# USB-HUB-MUX.net
KiCad netlist of a schematic drawn in Altium Designer
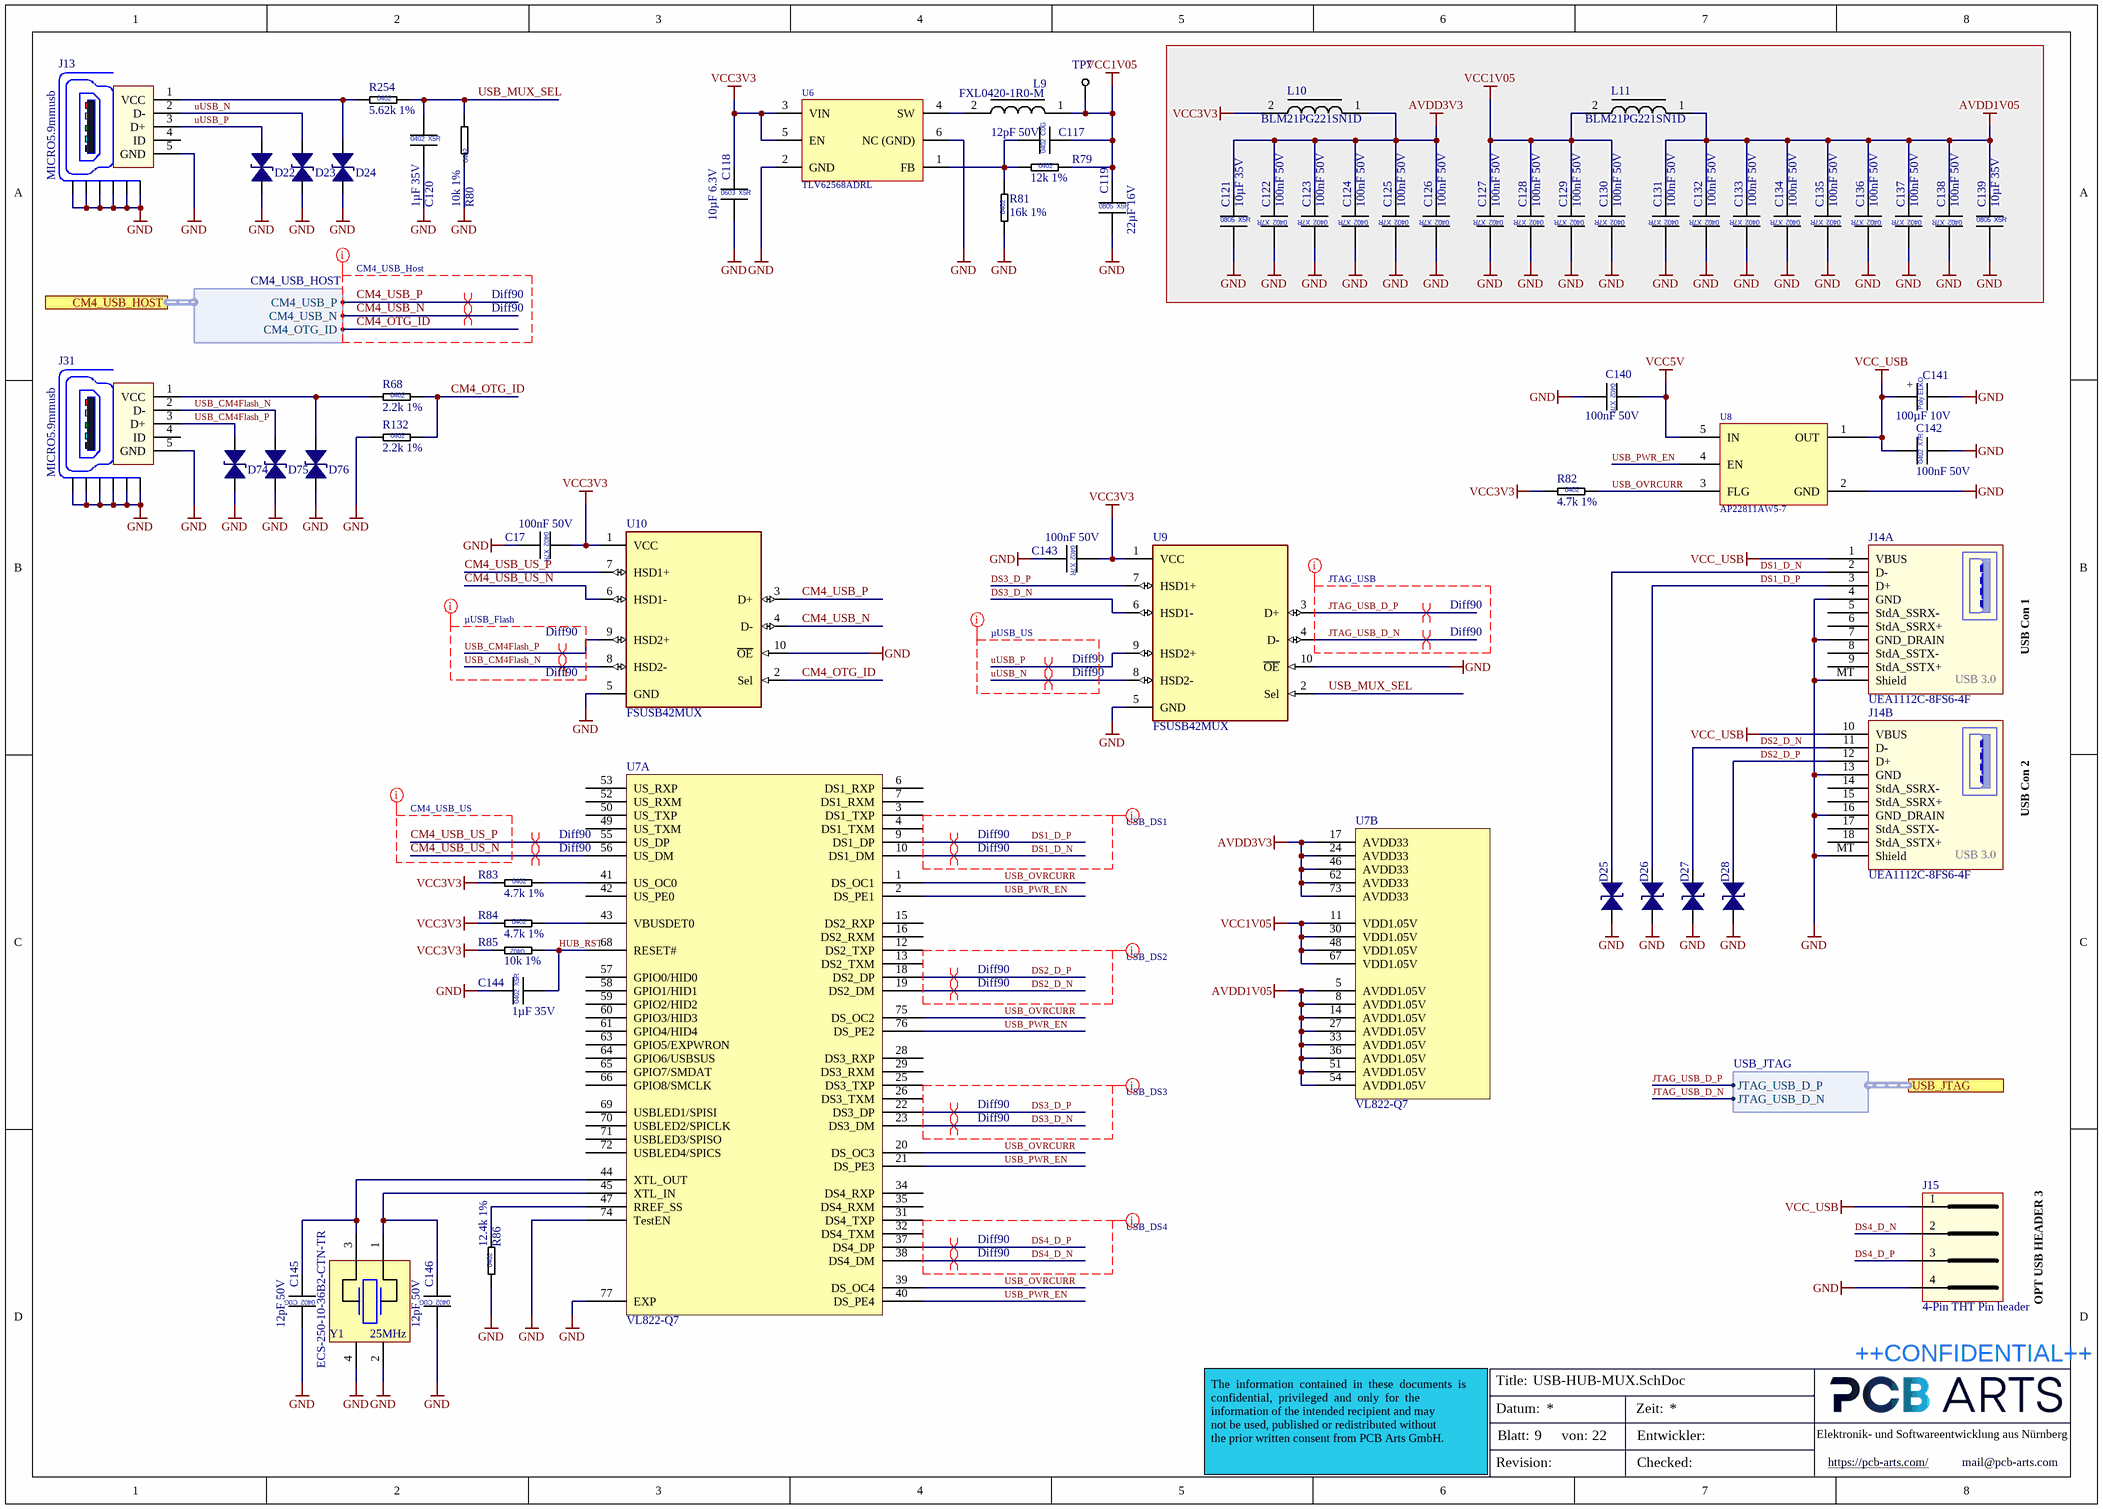
[diagram p0: USB-HUB-MUX.SchDoc]

(export (version "E")
  (design (tool "Eeschema 10.0.6"))
  (components
    (comp (ref "C17")
      (value "100nF 50V")
      (footprint "Cap:CAP_0402_L")
      (description "Multilayer Ceramic Capacitors MLCC - SMD/SMT 0402 50VDC")
      (libsource (lib "") (part "CAP_0402_100nF_50V_1"))
    )
    (comp (ref "C117")
      (value "12pF 50V")
      (footprint "Cap:CAP_0402_L")
      (description "Multilayer Ceramic Capacitors MLCC - SMD/SMT 0402 50VDC")
      (libsource (lib "Cap") (part "CAP_0402_12pF_50V"))
    )
    (comp (ref "C118")
      (value "10µF 6.3V")
      (footprint "Cap:CAP_0603_L")
      (description "Multilayer Ceramic Capacitors MLCC - SMD/SMT 0603 6.3VDC")
      (libsource (lib "Cap") (part "CAP_0603_10µF_6.3V"))
    )
    (comp (ref "C119")
      (value "22µF 16V")
      (footprint "Cap:CAP_0805")
      (description "Multilayer Ceramic Capacitors MLCC - SMD/SMT 0805 16VDC")
      (libsource (lib "Cap") (part "CAP_0805_22µF_16V"))
    )
    (comp (ref "C120")
      (value "1µF 35V")
      (footprint "Cap:CAP_0402_L")
      (description "Multilayer Ceramic Capacitors MLCC - SMD/SMT 0402 35VDC")
      (libsource (lib "Cap") (part "CAP_0402_1µF_35V"))
    )
    (comp (ref "C121")
      (value "10µF 35V")
      (footprint "Cap:CAP_0805")
      (description "Multilayer Ceramic Capacitors MLCC - SMD/SMT 0805 35VDC")
      (libsource (lib "Cap") (part "CAP_0805_10µF_35V"))
    )
    (comp (ref "C122")
      (value "100nF 50V")
      (footprint "Cap:CAP_0402_L")
      (description "Multilayer Ceramic Capacitors MLCC - SMD/SMT 0402 50VDC")
      (libsource (lib "Cap") (part "CAP_0402_100nF_50V"))
    )
    (comp (ref "C123")
      (value "100nF 50V")
      (footprint "Cap:CAP_0402_L")
      (description "Multilayer Ceramic Capacitors MLCC - SMD/SMT 0402 50VDC")
      (libsource (lib "Cap") (part "CAP_0402_100nF_50V"))
    )
    (comp (ref "C124")
      (value "100nF 50V")
      (footprint "Cap:CAP_0402_L")
      (description "Multilayer Ceramic Capacitors MLCC - SMD/SMT 0402 50VDC")
      (libsource (lib "Cap") (part "CAP_0402_100nF_50V"))
    )
    (comp (ref "C125")
      (value "100nF 50V")
      (footprint "Cap:CAP_0402_L")
      (description "Multilayer Ceramic Capacitors MLCC - SMD/SMT 0402 50VDC")
      (libsource (lib "Cap") (part "CAP_0402_100nF_50V"))
    )
    (comp (ref "C126")
      (value "100nF 50V")
      (footprint "Cap:CAP_0402_L")
      (description "Multilayer Ceramic Capacitors MLCC - SMD/SMT 0402 50VDC")
      (libsource (lib "Cap") (part "CAP_0402_100nF_50V"))
    )
    (comp (ref "C127")
      (value "100nF 50V")
      (footprint "Cap:CAP_0402_L")
      (description "Multilayer Ceramic Capacitors MLCC - SMD/SMT 0402 50VDC")
      (libsource (lib "Cap") (part "CAP_0402_100nF_50V"))
    )
    (comp (ref "C128")
      (value "100nF 50V")
      (footprint "Cap:CAP_0402_L")
      (description "Multilayer Ceramic Capacitors MLCC - SMD/SMT 0402 50VDC")
      (libsource (lib "Cap") (part "CAP_0402_100nF_50V"))
    )
    (comp (ref "C129")
      (value "100nF 50V")
      (footprint "Cap:CAP_0402_L")
      (description "Multilayer Ceramic Capacitors MLCC - SMD/SMT 0402 50VDC")
      (libsource (lib "Cap") (part "CAP_0402_100nF_50V"))
    )
    (comp (ref "C130")
      (value "100nF 50V")
      (footprint "Cap:CAP_0402_L")
      (description "Multilayer Ceramic Capacitors MLCC - SMD/SMT 0402 50VDC")
      (libsource (lib "Cap") (part "CAP_0402_100nF_50V"))
    )
    (comp (ref "C131")
      (value "100nF 50V")
      (footprint "Cap:CAP_0402_L")
      (description "Multilayer Ceramic Capacitors MLCC - SMD/SMT 0402 50VDC")
      (libsource (lib "Cap") (part "CAP_0402_100nF_50V"))
    )
    (comp (ref "C132")
      (value "100nF 50V")
      (footprint "Cap:CAP_0402_L")
      (description "Multilayer Ceramic Capacitors MLCC - SMD/SMT 0402 50VDC")
      (libsource (lib "Cap") (part "CAP_0402_100nF_50V"))
    )
    (comp (ref "C133")
      (value "100nF 50V")
      (footprint "Cap:CAP_0402_L")
      (description "Multilayer Ceramic Capacitors MLCC - SMD/SMT 0402 50VDC")
      (libsource (lib "Cap") (part "CAP_0402_100nF_50V"))
    )
    (comp (ref "C134")
      (value "100nF 50V")
      (footprint "Cap:CAP_0402_L")
      (description "Multilayer Ceramic Capacitors MLCC - SMD/SMT 0402 50VDC")
      (libsource (lib "Cap") (part "CAP_0402_100nF_50V"))
    )
    (comp (ref "C135")
      (value "100nF 50V")
      (footprint "Cap:CAP_0402_L")
      (description "Multilayer Ceramic Capacitors MLCC - SMD/SMT 0402 50VDC")
      (libsource (lib "Cap") (part "CAP_0402_100nF_50V"))
    )
    (comp (ref "C136")
      (value "100nF 50V")
      (footprint "Cap:CAP_0402_L")
      (description "Multilayer Ceramic Capacitors MLCC - SMD/SMT 0402 50VDC")
      (libsource (lib "Cap") (part "CAP_0402_100nF_50V"))
    )
    (comp (ref "C137")
      (value "100nF 50V")
      (footprint "Cap:CAP_0402_L")
      (description "Multilayer Ceramic Capacitors MLCC - SMD/SMT 0402 50VDC")
      (libsource (lib "Cap") (part "CAP_0402_100nF_50V"))
    )
    (comp (ref "C138")
      (value "100nF 50V")
      (footprint "Cap:CAP_0402_L")
      (description "Multilayer Ceramic Capacitors MLCC - SMD/SMT 0402 50VDC")
      (libsource (lib "Cap") (part "CAP_0402_100nF_50V"))
    )
    (comp (ref "C139")
      (value "10µF 35V")
      (footprint "Cap:CAP_0805")
      (description "Multilayer Ceramic Capacitors MLCC - SMD/SMT 0805 35VDC")
      (libsource (lib "Cap") (part "CAP_0805_10µF_35V"))
    )
    (comp (ref "C140")
      (value "100nF 50V")
      (footprint "Cap:CAP_0402_L")
      (description "Multilayer Ceramic Capacitors MLCC - SMD/SMT 0402 50VDC")
      (libsource (lib "") (part "CAP_0402_100nF_50V_1"))
    )
    (comp (ref "C141")
      (value "100µF 10V")
      (footprint "Cap:WCAP-ASLI_D5H5.5")
      (description "Organische Polymer-Aluminiumkondensatoren 100uF 10 Volts 20%")
      (libsource (lib "Cap") (part "CAP_D5L5.5_100µF_10V"))
    )
    (comp (ref "C142")
      (value "100nF 50V")
      (footprint "Cap:CAP_0402_L")
      (description "Multilayer Ceramic Capacitors MLCC - SMD/SMT 0402 50VDC")
      (libsource (lib "Cap") (part "CAP_0402_100nF_50V"))
    )
    (comp (ref "C143")
      (value "100nF 50V")
      (footprint "Cap:CAP_0402_L")
      (description "Multilayer Ceramic Capacitors MLCC - SMD/SMT 0402 50VDC")
      (libsource (lib "") (part "CAP_0402_100nF_50V_1"))
    )
    (comp (ref "C144")
      (value "1µF 35V")
      (footprint "Cap:CAP_0402_L")
      (description "Multilayer Ceramic Capacitors MLCC - SMD/SMT 0402 35VDC")
      (libsource (lib "") (part "CAP_0402_1µF_35V_1"))
    )
    (comp (ref "C145")
      (value "12pF 50V")
      (footprint "Cap:CAP_0402_L")
      (description "Multilayer Ceramic Capacitors MLCC - SMD/SMT 0402 50VDC")
      (libsource (lib "Cap") (part "CAP_0402_12pF_50V"))
    )
    (comp (ref "C146")
      (value "12pF 50V")
      (footprint "Cap:CAP_0402_L")
      (description "Multilayer Ceramic Capacitors MLCC - SMD/SMT 0402 50VDC")
      (libsource (lib "Cap") (part "CAP_0402_12pF_50V"))
    )
    (comp (ref "D22")
      (value "CESDP0402UC5VB")
      (footprint "Protec:TVS_0402")
      (description "Low Capacitance ESD Protection Diode 0402")
      (libsource (lib "Protec") (part "CESDP0402UC5VB_TVS Diode 0402"))
    )
    (comp (ref "D23")
      (value "CESDP0402UC5VB")
      (footprint "Protec:TVS_0402")
      (description "Low Capacitance ESD Protection Diode 0402")
      (libsource (lib "Protec") (part "CESDP0402UC5VB_TVS Diode 0402"))
    )
    (comp (ref "D24")
      (value "CESDP0402UC5VB")
      (footprint "Protec:TVS_0402")
      (description "Low Capacitance ESD Protection Diode 0402")
      (libsource (lib "Protec") (part "CESDP0402UC5VB_TVS Diode 0402"))
    )
    (comp (ref "D25")
      (value "CESDP0402UC5VB")
      (footprint "Protec:TVS_0402")
      (description "Low Capacitance ESD Protection Diode 0402")
      (libsource (lib "Protec") (part "CESDP0402UC5VB_TVS Diode 0402"))
    )
    (comp (ref "D26")
      (value "CESDP0402UC5VB")
      (footprint "Protec:TVS_0402")
      (description "Low Capacitance ESD Protection Diode 0402")
      (libsource (lib "Protec") (part "CESDP0402UC5VB_TVS Diode 0402"))
    )
    (comp (ref "D27")
      (value "CESDP0402UC5VB")
      (footprint "Protec:TVS_0402")
      (description "Low Capacitance ESD Protection Diode 0402")
      (libsource (lib "Protec") (part "CESDP0402UC5VB_TVS Diode 0402"))
    )
    (comp (ref "D28")
      (value "CESDP0402UC5VB")
      (footprint "Protec:TVS_0402")
      (description "Low Capacitance ESD Protection Diode 0402")
      (libsource (lib "Protec") (part "CESDP0402UC5VB_TVS Diode 0402"))
    )
    (comp (ref "D74")
      (value "CESDP0402UC5VB")
      (footprint "Protec:TVS_0402")
      (description "Low Capacitance ESD Protection Diode 0402")
      (libsource (lib "Protec") (part "CESDP0402UC5VB_TVS Diode 0402"))
    )
    (comp (ref "D75")
      (value "CESDP0402UC5VB")
      (footprint "Protec:TVS_0402")
      (description "Low Capacitance ESD Protection Diode 0402")
      (libsource (lib "Protec") (part "CESDP0402UC5VB_TVS Diode 0402"))
    )
    (comp (ref "D76")
      (value "CESDP0402UC5VB")
      (footprint "Protec:TVS_0402")
      (description "Low Capacitance ESD Protection Diode 0402")
      (libsource (lib "Protec") (part "CESDP0402UC5VB_TVS Diode 0402"))
    )
    (comp (ref "J13")
      (value "MICRO5.9mmusb")
      (footprint "Conn:MICRO5.9mmusb")
      (description "SHOU HAN  MICRO5.9mmusb")
      (libsource (lib "Conn") (part "SMD micro USB Connector Horizontal C393940"))
    )
    (comp (ref "J14")
      (value "UEA1112C-8FS6-4F")
      (footprint "CONN:UEA1112C-8FS6-4F")
      (description "Dual USB 3.0 Horizontal Type A")
      (libsource (lib "Conn") (part "UEA1112C-8FS6-4F_Dual USB 3.0 Horizontal Type A_1"))
    )
    (comp (ref "J15")
      (value "4-Pin THT Pin header")
      (footprint "Conn:61300411121")
      (description "WR-PHD 2.54mm 4Pin THT Header")
      (libsource (lib "Conn") (part "61300411121_WR-PHD 2.54mm 4Pin THT Header"))
    )
    (comp (ref "J31")
      (value "MICRO5.9mmusb")
      (footprint "Conn:MICRO5.9mmusb")
      (description "SHOU HAN  MICRO5.9mmusb")
      (libsource (lib "Conn") (part "SMD micro USB Connector Horizontal C393940"))
    )
    (comp (ref "L9")
      (value "FXL0420-1R0-M")
      (footprint "Indc:FXL0420-1R0-M")
      (description "1uH ±20% 6A 27mΩ SMD,4.4x4.5x1.8mm Power Inductor")
      (libsource (lib "Indc") (part "1uH 6A 27mΩ  FXL0420-1R0-M"))
    )
    (comp (ref "L10")
      (value "BLM21PG221SN1D")
      (footprint "indc:L_0805")
      (description "Ferrite Beads 0805 220 OHM")
      (libsource (lib "Indc") (part "Ferrite Beads 0805 220 OHM BLM21PG221SN1D"))
    )
    (comp (ref "L11")
      (value "BLM21PG221SN1D")
      (footprint "indc:L_0805")
      (description "Ferrite Beads 0805 220 OHM")
      (libsource (lib "Indc") (part "Ferrite Beads 0805 220 OHM BLM21PG221SN1D"))
    )
    (comp (ref "R68")
      (value "2.2k 1%")
      (footprint "Res:RES_0402_L")
      (description "Thick Film Resistors - SMD 2.2kOhm 1%")
      (libsource (lib "Res") (part "RES_0402_2.2k_1%"))
    )
    (comp (ref "R79")
      (value "12k 1%")
      (footprint "Res:RES_0402_L")
      (description "Thick Film Resistors - SMD 12kOhm 1%")
      (libsource (lib "Res") (part "RES_0402_12k_1%"))
    )
    (comp (ref "R80")
      (value "10k 1%")
      (footprint "Res:RES_0402_L")
      (description "Thick Film Resistors - SMD 10kOhm 1%")
      (libsource (lib "Res") (part "RES_0402_10k_1%"))
    )
    (comp (ref "R81")
      (value "16k 1%")
      (footprint "Res:RES_0402_L")
      (description "Thick Film Resistors - SMD 16kOhm 1%")
      (libsource (lib "Res") (part "RES_0402_16k_1%"))
    )
    (comp (ref "R82")
      (value "4.7k 1%")
      (footprint "Res:RES_0402_L")
      (description "Thick Film Resistors - SMD 4.7kOhm 1%")
      (libsource (lib "Res") (part "RES_0402_4.7k_1%"))
    )
    (comp (ref "R83")
      (value "4.7k 1%")
      (footprint "Res:RES_0402_L")
      (description "Thick Film Resistors - SMD 4.7kOhm 1%")
      (libsource (lib "Res") (part "RES_0402_4.7k_1%"))
    )
    (comp (ref "R84")
      (value "4.7k 1%")
      (footprint "Res:RES_0402_L")
      (description "Thick Film Resistors - SMD 4.7kOhm 1%")
      (libsource (lib "Res") (part "RES_0402_4.7k_1%"))
    )
    (comp (ref "R85")
      (value "10k 1%")
      (footprint "Res:RES_0402_L")
      (description "Thick Film Resistors - SMD 10kOhm 1%")
      (libsource (lib "Res") (part "RES_0402_10k_1%"))
    )
    (comp (ref "R86")
      (value "12.4k 1%")
      (footprint "Res:RES_0402_L")
      (description "Thick Film Resistors - SMD 12.4kOhm 1%")
      (libsource (lib "Res") (part "RES_0402_12.4k_1%"))
    )
    (comp (ref "R132")
      (value "2.2k 1%")
      (footprint "Res:RES_0402_L")
      (description "Thick Film Resistors - SMD 2.2kOhm 1%")
      (libsource (lib "Res") (part "RES_0402_2.2k_1%"))
    )
    (comp (ref "R254")
      (value "5.62k 1%")
      (footprint "Res:RES_0402_L")
      (description "Thick Film Resistors - SMD 5.62kOhm 1%")
      (libsource (lib "Res") (part "RES_0402_5.62k_1%"))
    )
    (comp (ref "TP7")
      (value "Testpoint")
      (footprint "Electro_mech:Testpoint 0.8mm")
      (description "Testpoint 0.8mm")
      (libsource (lib "Electro_Mech") (part "Testpoint 0.8mm"))
    )
    (comp (ref "U6")
      (value "TLV62568ADRL")
      (footprint "Power:SON50P150X80-6N")
      (description "Step Down Converter with Forced PWM in SOT563 Package")
      (libsource (lib "Power") (part "TLV62568ADRL_Step Down Converter 1A; 2A"))
    )
    (comp (ref "U7")
      (value "VL822-Q7")
      (footprint "Digital:QFN50P900X900X85-76N")
      (description "USB Interface IC  USB 3.1 Hub 4 Ports")
      (libsource (lib "Digital") (part "VL822-Q7_USB Interface IC  USB 3.1 Hub 4 Ports"))
    )
    (comp (ref "U8")
      (value "AP22811AW5-7")
      (footprint "Power:SOT95P285X140-5N")
      (description "Power Switch ICs - Power Distribution Load Switch")
      (libsource (lib "Power") (part "AP22811AW5-7_Power Switch ICs - Power Distribution Load Switch"))
    )
    (comp (ref "U9")
      (value "FSUSB42MUX")
      (footprint "digital:SOP50P300X300X110-10N")
      (description "IC USB SWITCH DPDT")
      (libsource (lib "Digital") (part "FSUSB42MUX_IC USB SWITCH DPDT"))
    )
    (comp (ref "U10")
      (value "FSUSB42MUX")
      (footprint "digital:SOP50P300X300X110-10N")
      (description "IC USB SWITCH DPDT")
      (libsource (lib "Digital") (part "FSUSB42MUX_IC USB SWITCH DPDT"))
    )
    (comp (ref "Y1")
      (value "ECS-250-10-36B2-CTN-TR")
      (footprint "Timer:ECX-2236B")
      (description "2.5 x 2.0 x 0.55 mm SMD Crystal")
      (fields (field (name "FREQUENCY") "25MHz"))
      (libsource (lib "Timer") (part "Quarz 25MHz ESR 50R10pF"))
    )
  )
  (nets
    (net (code "3") (name "/CM4_OTG_ID") (class "Default")
      (node (ref "R132") (pin "2") (pinfunction "2_2") (pintype "passive"))
      (node (ref "R68") (pin "2") (pinfunction "2_2") (pintype "passive"))
      (node (ref "U10") (pin "2") (pinfunction "Sel_2") (pintype "input"))
    )
    (net (code "4") (name "/CM4_USB_N") (class "Default")
      (node (ref "U10") (pin "4") (pinfunction "D-_4") (pintype "bidirectional"))
    )
    (net (code "5") (name "/CM4_USB_P") (class "Default")
      (node (ref "U10") (pin "3") (pinfunction "D+_3") (pintype "bidirectional"))
    )
    (net (code "6") (name "/CM4_USB_US_N") (class "Default")
      (node (ref "U10") (pin "6") (pinfunction "HSD1-_6") (pintype "bidirectional"))
      (node (ref "U7") (pin "56") (pinfunction "US_DM_56") (pintype "passive"))
    )
    (net (code "7") (name "/CM4_USB_US_P") (class "Default")
      (node (ref "U10") (pin "7") (pinfunction "HSD1+_7") (pintype "bidirectional"))
      (node (ref "U7") (pin "55") (pinfunction "US_DP_55") (pintype "passive"))
    )
    (net (code "8") (name "/DS1_D_N") (class "Default")
      (node (ref "D25") (pin "2") (pinfunction "2_2") (pintype "passive"))
      (node (ref "J14") (pin "2") (pinfunction "D-_2") (pintype "passive"))
      (node (ref "U7") (pin "10") (pinfunction "DS1_DM_10") (pintype "passive"))
    )
    (net (code "9") (name "/DS1_D_P") (class "Default")
      (node (ref "D26") (pin "2") (pinfunction "2_2") (pintype "passive"))
      (node (ref "J14") (pin "3") (pinfunction "D+_3") (pintype "passive"))
      (node (ref "U7") (pin "9") (pinfunction "DS1_DP_9") (pintype "passive"))
    )
    (net (code "10") (name "/DS2_D_N") (class "Default")
      (node (ref "D27") (pin "2") (pinfunction "2_2") (pintype "passive"))
      (node (ref "J14") (pin "11") (pinfunction "D-_11") (pintype "passive"))
      (node (ref "U7") (pin "19") (pinfunction "DS2_DM_19") (pintype "passive"))
    )
    (net (code "11") (name "/DS2_D_P") (class "Default")
      (node (ref "D28") (pin "2") (pinfunction "2_2") (pintype "passive"))
      (node (ref "J14") (pin "12") (pinfunction "D+_12") (pintype "passive"))
      (node (ref "U7") (pin "18") (pinfunction "DS2_DP_18") (pintype "passive"))
    )
    (net (code "12") (name "/DS3_D_N") (class "Default")
      (node (ref "U7") (pin "23") (pinfunction "DS3_DM_23") (pintype "passive"))
      (node (ref "U9") (pin "6") (pinfunction "HSD1-_6") (pintype "bidirectional"))
    )
    (net (code "13") (name "/DS3_D_P") (class "Default")
      (node (ref "U7") (pin "22") (pinfunction "DS3_DP_22") (pintype "passive"))
      (node (ref "U9") (pin "7") (pinfunction "HSD1+_7") (pintype "bidirectional"))
    )
    (net (code "14") (name "/DS4_D_N") (class "Default")
      (node (ref "J15") (pin "2") (pinfunction "2_2") (pintype "passive"))
      (node (ref "U7") (pin "38") (pinfunction "DS4_DM_38") (pintype "passive"))
    )
    (net (code "15") (name "/DS4_D_P") (class "Default")
      (node (ref "J15") (pin "3") (pinfunction "3_3") (pintype "passive"))
      (node (ref "U7") (pin "37") (pinfunction "DS4_DP_37") (pintype "passive"))
    )
    (net (code "16") (name "/HUB_RST") (class "Default")
      (node (ref "C144") (pin "2") (pinfunction "2_2") (pintype "passive"))
      (node (ref "R85") (pin "1") (pinfunction "1_1") (pintype "passive"))
      (node (ref "U7") (pin "68") (pinfunction "RESET#_68") (pintype "passive"))
    )
    (net (code "17") (name "/JTAG_USB_D_N") (class "Default")
      (node (ref "U9") (pin "4") (pinfunction "D-_4") (pintype "bidirectional"))
    )
    (net (code "18") (name "/JTAG_USB_D_P") (class "Default")
      (node (ref "U9") (pin "3") (pinfunction "D+_3") (pintype "bidirectional"))
    )
    (net (code "19") (name "/USB_CM4Flash_N") (class "Default")
      (node (ref "D75") (pin "1") (pinfunction "1_1") (pintype "passive"))
      (node (ref "J31") (pin "2") (pinfunction "D-_2") (pintype "passive"))
      (node (ref "U10") (pin "8") (pinfunction "HSD2-_8") (pintype "bidirectional"))
    )
    (net (code "20") (name "/USB_CM4Flash_P") (class "Default")
      (node (ref "D74") (pin "1") (pinfunction "1_1") (pintype "passive"))
      (node (ref "J31") (pin "3") (pinfunction "D+_3") (pintype "passive"))
      (node (ref "U10") (pin "9") (pinfunction "HSD2+_9") (pintype "bidirectional"))
    )
    (net (code "21") (name "/USB_MUX_SEL") (class "Default")
      (node (ref "C120") (pin "1") (pinfunction "1_1") (pintype "passive"))
      (node (ref "R254") (pin "2") (pinfunction "2_2") (pintype "passive"))
      (node (ref "R80") (pin "2") (pinfunction "2_2") (pintype "passive"))
      (node (ref "U9") (pin "2") (pinfunction "Sel_2") (pintype "input"))
    )
    (net (code "22") (name "/USB_OVRCURR") (class "Default")
      (node (ref "R82") (pin "2") (pinfunction "2_2") (pintype "passive"))
      (node (ref "U7") (pin "1") (pinfunction "DS_OC1_1") (pintype "passive"))
      (node (ref "U7") (pin "20") (pinfunction "DS_OC3_20") (pintype "passive"))
      (node (ref "U7") (pin "39") (pinfunction "DS_OC4_39") (pintype "passive"))
      (node (ref "U7") (pin "75") (pinfunction "DS_OC2_75") (pintype "passive"))
      (node (ref "U8") (pin "3") (pinfunction "FLG_3") (pintype "open_collector"))
    )
    (net (code "23") (name "/USB_PWR_EN") (class "Default")
      (node (ref "U7") (pin "2") (pinfunction "DS_PE1_2") (pintype "passive"))
      (node (ref "U7") (pin "21") (pinfunction "DS_PE3_21") (pintype "passive"))
      (node (ref "U7") (pin "40") (pinfunction "DS_PE4_40") (pintype "passive"))
      (node (ref "U7") (pin "76") (pinfunction "DS_PE2_76") (pintype "passive"))
      (node (ref "U8") (pin "4") (pinfunction "EN_4") (pintype "passive"))
    )
    (net (code "24") (name "/uUSB_N") (class "Default")
      (node (ref "D23") (pin "1") (pinfunction "1_1") (pintype "passive"))
      (node (ref "J13") (pin "2") (pinfunction "D-_2") (pintype "passive"))
      (node (ref "U9") (pin "8") (pinfunction "HSD2-_8") (pintype "bidirectional"))
    )
    (net (code "25") (name "/uUSB_P") (class "Default")
      (node (ref "D22") (pin "1") (pinfunction "1_1") (pintype "passive"))
      (node (ref "J13") (pin "3") (pinfunction "D+_3") (pintype "passive"))
      (node (ref "U9") (pin "9") (pinfunction "HSD2+_9") (pintype "bidirectional"))
    )
    (net (code "28") (name "AVDD1V05") (class "Default")
      (node (ref "C131") (pin "2") (pinfunction "2_2") (pintype "passive"))
      (node (ref "C132") (pin "2") (pinfunction "2_2") (pintype "passive"))
      (node (ref "C133") (pin "2") (pinfunction "2_2") (pintype "passive"))
      (node (ref "C134") (pin "2") (pinfunction "2_2") (pintype "passive"))
      (node (ref "C135") (pin "2") (pinfunction "2_2") (pintype "passive"))
      (node (ref "C136") (pin "2") (pinfunction "2_2") (pintype "passive"))
      (node (ref "C137") (pin "2") (pinfunction "2_2") (pintype "passive"))
      (node (ref "C138") (pin "2") (pinfunction "2_2") (pintype "passive"))
      (node (ref "C139") (pin "1") (pinfunction "1_1") (pintype "passive"))
      (node (ref "L11") (pin "1") (pinfunction "1_1") (pintype "passive"))
      (node (ref "U7") (pin "14") (pinfunction "AVDD1.05V_14") (pintype "passive"))
      (node (ref "U7") (pin "27") (pinfunction "AVDD1.05V_27") (pintype "passive"))
      (node (ref "U7") (pin "33") (pinfunction "AVDD1.05V_33") (pintype "passive"))
      (node (ref "U7") (pin "36") (pinfunction "AVDD1.05V_36") (pintype "passive"))
      (node (ref "U7") (pin "5") (pinfunction "AVDD1.05V_5") (pintype "passive"))
      (node (ref "U7") (pin "51") (pinfunction "AVDD1.05V_51") (pintype "passive"))
      (node (ref "U7") (pin "54") (pinfunction "AVDD1.05V_54") (pintype "passive"))
      (node (ref "U7") (pin "8") (pinfunction "AVDD1.05V_8") (pintype "passive"))
    )
    (net (code "29") (name "AVDD3V3") (class "Default")
      (node (ref "C121") (pin "1") (pinfunction "1_1") (pintype "passive"))
      (node (ref "C122") (pin "2") (pinfunction "2_2") (pintype "passive"))
      (node (ref "C123") (pin "2") (pinfunction "2_2") (pintype "passive"))
      (node (ref "C124") (pin "2") (pinfunction "2_2") (pintype "passive"))
      (node (ref "C125") (pin "2") (pinfunction "2_2") (pintype "passive"))
      (node (ref "C126") (pin "2") (pinfunction "2_2") (pintype "passive"))
      (node (ref "L10") (pin "1") (pinfunction "1_1") (pintype "passive"))
      (node (ref "U7") (pin "17") (pinfunction "AVDD33_17") (pintype "passive"))
      (node (ref "U7") (pin "24") (pinfunction "AVDD33_24") (pintype "passive"))
      (node (ref "U7") (pin "46") (pinfunction "AVDD33_46") (pintype "passive"))
      (node (ref "U7") (pin "62") (pinfunction "AVDD33_62") (pintype "passive"))
      (node (ref "U7") (pin "73") (pinfunction "AVDD33_73") (pintype "passive"))
    )
    (net (code "30") (name "GND") (class "Default")
      (node (ref "C118") (pin "2") (pinfunction "2_2") (pintype "passive"))
      (node (ref "C119") (pin "2") (pinfunction "2_2") (pintype "passive"))
      (node (ref "C120") (pin "2") (pinfunction "2_2") (pintype "passive"))
      (node (ref "C121") (pin "2") (pinfunction "2_2") (pintype "passive"))
      (node (ref "C122") (pin "1") (pinfunction "1_1") (pintype "passive"))
      (node (ref "C123") (pin "1") (pinfunction "1_1") (pintype "passive"))
      (node (ref "C124") (pin "1") (pinfunction "1_1") (pintype "passive"))
      (node (ref "C125") (pin "1") (pinfunction "1_1") (pintype "passive"))
      (node (ref "C126") (pin "1") (pinfunction "1_1") (pintype "passive"))
      (node (ref "C127") (pin "1") (pinfunction "1_1") (pintype "passive"))
      (node (ref "C128") (pin "1") (pinfunction "1_1") (pintype "passive"))
      (node (ref "C129") (pin "1") (pinfunction "1_1") (pintype "passive"))
      (node (ref "C130") (pin "1") (pinfunction "1_1") (pintype "passive"))
      (node (ref "C131") (pin "1") (pinfunction "1_1") (pintype "passive"))
      (node (ref "C132") (pin "1") (pinfunction "1_1") (pintype "passive"))
      (node (ref "C133") (pin "1") (pinfunction "1_1") (pintype "passive"))
      (node (ref "C134") (pin "1") (pinfunction "1_1") (pintype "passive"))
      (node (ref "C135") (pin "1") (pinfunction "1_1") (pintype "passive"))
      (node (ref "C136") (pin "1") (pinfunction "1_1") (pintype "passive"))
      (node (ref "C137") (pin "1") (pinfunction "1_1") (pintype "passive"))
      (node (ref "C138") (pin "1") (pinfunction "1_1") (pintype "passive"))
      (node (ref "C139") (pin "2") (pinfunction "2_2") (pintype "passive"))
      (node (ref "C140") (pin "2") (pinfunction "2_2") (pintype "passive"))
      (node (ref "C141") (pin "2") (pinfunction "2_2") (pintype "passive"))
      (node (ref "C142") (pin "2") (pinfunction "2_2") (pintype "passive"))
      (node (ref "C143") (pin "2") (pinfunction "2_2") (pintype "passive"))
      (node (ref "C144") (pin "1") (pinfunction "1_1") (pintype "passive"))
      (node (ref "C145") (pin "1") (pinfunction "1_1") (pintype "passive"))
      (node (ref "C146") (pin "1") (pinfunction "1_1") (pintype "passive"))
      (node (ref "C17") (pin "2") (pinfunction "2_2") (pintype "passive"))
      (node (ref "D22") (pin "2") (pinfunction "2_2") (pintype "passive"))
      (node (ref "D23") (pin "2") (pinfunction "2_2") (pintype "passive"))
      (node (ref "D24") (pin "2") (pinfunction "2_2") (pintype "passive"))
      (node (ref "D25") (pin "1") (pinfunction "1_1") (pintype "passive"))
      (node (ref "D26") (pin "1") (pinfunction "1_1") (pintype "passive"))
      (node (ref "D27") (pin "1") (pinfunction "1_1") (pintype "passive"))
      (node (ref "D28") (pin "1") (pinfunction "1_1") (pintype "passive"))
      (node (ref "D74") (pin "2") (pinfunction "2_2") (pintype "passive"))
      (node (ref "D75") (pin "2") (pinfunction "2_2") (pintype "passive"))
      (node (ref "D76") (pin "2") (pinfunction "2_2") (pintype "passive"))
      (node (ref "J13") (pin "10") (pinfunction "Shield_10") (pintype "passive"))
      (node (ref "J13") (pin "11") (pinfunction "Shield_11") (pintype "passive"))
      (node (ref "J13") (pin "5") (pinfunction "GND_5") (pintype "passive"))
      (node (ref "J13") (pin "6") (pinfunction "Shield_6") (pintype "passive"))
      (node (ref "J13") (pin "7") (pinfunction "Shield_7") (pintype "passive"))
      (node (ref "J13") (pin "8") (pinfunction "Shield_8") (pintype "passive"))
      (node (ref "J13") (pin "9") (pinfunction "Shield_9") (pintype "passive"))
      (node (ref "J14") (pin "13") (pinfunction "GND_13") (pintype "passive"))
      (node (ref "J14") (pin "16") (pinfunction "GND_DRAIN_16") (pintype "passive"))
      (node (ref "J14") (pin "4") (pinfunction "GND_4") (pintype "passive"))
      (node (ref "J14") (pin "7") (pinfunction "GND_DRAIN_7") (pintype "passive"))
      (node (ref "J14") (pin "MT") (pinfunction "Shield_MT") (pintype "passive"))
      (node (ref "J15") (pin "4") (pinfunction "4_4") (pintype "passive"))
      (node (ref "J31") (pin "10") (pinfunction "Shield_10") (pintype "passive"))
      (node (ref "J31") (pin "11") (pinfunction "Shield_11") (pintype "passive"))
      (node (ref "J31") (pin "5") (pinfunction "GND_5") (pintype "passive"))
      (node (ref "J31") (pin "6") (pinfunction "Shield_6") (pintype "passive"))
      (node (ref "J31") (pin "7") (pinfunction "Shield_7") (pintype "passive"))
      (node (ref "J31") (pin "8") (pinfunction "Shield_8") (pintype "passive"))
      (node (ref "J31") (pin "9") (pinfunction "Shield_9") (pintype "passive"))
      (node (ref "R132") (pin "1") (pinfunction "1_1") (pintype "passive"))
      (node (ref "R80") (pin "1") (pinfunction "1_1") (pintype "passive"))
      (node (ref "R81") (pin "1") (pinfunction "1_1") (pintype "passive"))
      (node (ref "R86") (pin "1") (pinfunction "1_1") (pintype "passive"))
      (node (ref "U10") (pin "10") (pinfunction "~{OE}_10") (pintype "input"))
      (node (ref "U10") (pin "5") (pinfunction "GND_5") (pintype "power_in"))
      (node (ref "U6") (pin "2") (pinfunction "GND_2") (pintype "passive"))
      (node (ref "U6") (pin "6") (pinfunction "NC_(GND)_6") (pintype "passive"))
      (node (ref "U7") (pin "74") (pinfunction "TestEN_74") (pintype "passive"))
      (node (ref "U7") (pin "77") (pinfunction "EXP_77") (pintype "passive"))
      (node (ref "U8") (pin "2") (pinfunction "GND_2") (pintype "power_in"))
      (node (ref "U9") (pin "10") (pinfunction "~{OE}_10") (pintype "input"))
      (node (ref "U9") (pin "5") (pinfunction "GND_5") (pintype "power_in"))
      (node (ref "Y1") (pin "2") (pinfunction "2_2") (pintype "passive"))
      (node (ref "Y1") (pin "4") (pinfunction "4_4") (pintype "passive"))
    )
    (net (code "31") (name "Net-(J13-VCC)") (class "Default")
      (node (ref "D24") (pin "1") (pinfunction "1_1") (pintype "passive"))
      (node (ref "J13") (pin "1") (pinfunction "VCC_1") (pintype "passive"))
      (node (ref "R254") (pin "1") (pinfunction "1_1") (pintype "passive"))
    )
    (net (code "32") (name "Net-(J31-VCC)") (class "Default")
      (node (ref "D76") (pin "1") (pinfunction "1_1") (pintype "passive"))
      (node (ref "J31") (pin "1") (pinfunction "VCC_1") (pintype "passive"))
      (node (ref "R68") (pin "1") (pinfunction "1_1") (pintype "passive"))
    )
    (net (code "33") (name "Net-(U6-FB)") (class "Default")
      (node (ref "C117") (pin "1") (pinfunction "1_1") (pintype "passive"))
      (node (ref "R79") (pin "1") (pinfunction "1_1") (pintype "passive"))
      (node (ref "R81") (pin "2") (pinfunction "2_2") (pintype "passive"))
      (node (ref "U6") (pin "1") (pinfunction "FB_1") (pintype "passive"))
    )
    (net (code "34") (name "Net-(U6-SW)") (class "Default")
      (node (ref "L9") (pin "2") (pinfunction "2_2") (pintype "passive"))
      (node (ref "U6") (pin "4") (pinfunction "SW_4") (pintype "passive"))
    )
    (net (code "35") (name "Net-(U7A-RREF_SS)") (class "Default")
      (node (ref "R86") (pin "2") (pinfunction "2_2") (pintype "passive"))
      (node (ref "U7") (pin "47") (pinfunction "RREF_SS_47") (pintype "passive"))
    )
    (net (code "36") (name "Net-(U7A-US_OC0)") (class "Default")
      (node (ref "R83") (pin "2") (pinfunction "2_2") (pintype "passive"))
      (node (ref "U7") (pin "41") (pinfunction "US_OC0_41") (pintype "passive"))
    )
    (net (code "37") (name "Net-(U7A-VBUSDET0)") (class "Default")
      (node (ref "R84") (pin "2") (pinfunction "2_2") (pintype "passive"))
      (node (ref "U7") (pin "43") (pinfunction "VBUSDET0_43") (pintype "passive"))
    )
    (net (code "38") (name "Net-(U7A-XTL_IN)") (class "Default")
      (node (ref "C146") (pin "2") (pinfunction "2_2") (pintype "passive"))
      (node (ref "U7") (pin "45") (pinfunction "XTL_IN_45") (pintype "passive"))
      (node (ref "Y1") (pin "1") (pinfunction "1_1") (pintype "passive"))
    )
    (net (code "39") (name "Net-(U7A-XTL_OUT)") (class "Default")
      (node (ref "C145") (pin "2") (pinfunction "2_2") (pintype "passive"))
      (node (ref "U7") (pin "44") (pinfunction "XTL_OUT_44") (pintype "passive"))
      (node (ref "Y1") (pin "3") (pinfunction "3_3") (pintype "passive"))
    )
    (net (code "40") (name "VCC1V05") (class "Default")
      (node (ref "C117") (pin "2") (pinfunction "2_2") (pintype "passive"))
      (node (ref "C119") (pin "1") (pinfunction "1_1") (pintype "passive"))
      (node (ref "C127") (pin "2") (pinfunction "2_2") (pintype "passive"))
      (node (ref "C128") (pin "2") (pinfunction "2_2") (pintype "passive"))
      (node (ref "C129") (pin "2") (pinfunction "2_2") (pintype "passive"))
      (node (ref "C130") (pin "2") (pinfunction "2_2") (pintype "passive"))
      (node (ref "L11") (pin "2") (pinfunction "2_2") (pintype "passive"))
      (node (ref "L9") (pin "1") (pinfunction "1_1") (pintype "passive"))
      (node (ref "R79") (pin "2") (pinfunction "2_2") (pintype "passive"))
      (node (ref "TP7") (pin "1") (pinfunction "GND_1") (pintype "passive"))
      (node (ref "U7") (pin "11") (pinfunction "VDD1.05V_11") (pintype "passive"))
      (node (ref "U7") (pin "30") (pinfunction "VDD1.05V_30") (pintype "passive"))
      (node (ref "U7") (pin "48") (pinfunction "VDD1.05V_48") (pintype "passive"))
      (node (ref "U7") (pin "67") (pinfunction "VDD1.05V_67") (pintype "passive"))
    )
    (net (code "41") (name "VCC3V3") (class "Default")
      (node (ref "C118") (pin "1") (pinfunction "1_1") (pintype "passive"))
      (node (ref "C143") (pin "1") (pinfunction "1_1") (pintype "passive"))
      (node (ref "C17") (pin "1") (pinfunction "1_1") (pintype "passive"))
      (node (ref "L10") (pin "2") (pinfunction "2_2") (pintype "passive"))
      (node (ref "R82") (pin "1") (pinfunction "1_1") (pintype "passive"))
      (node (ref "R83") (pin "1") (pinfunction "1_1") (pintype "passive"))
      (node (ref "R84") (pin "1") (pinfunction "1_1") (pintype "passive"))
      (node (ref "R85") (pin "2") (pinfunction "2_2") (pintype "passive"))
      (node (ref "U10") (pin "1") (pinfunction "VCC_1") (pintype "power_in"))
      (node (ref "U6") (pin "3") (pinfunction "VIN_3") (pintype "passive"))
      (node (ref "U6") (pin "5") (pinfunction "EN_5") (pintype "passive"))
      (node (ref "U9") (pin "1") (pinfunction "VCC_1") (pintype "power_in"))
    )
    (net (code "42") (name "VCC5V") (class "Default")
      (node (ref "C140") (pin "1") (pinfunction "1_1") (pintype "passive"))
      (node (ref "U8") (pin "5") (pinfunction "IN_5") (pintype "power_in"))
    )
    (net (code "43") (name "VCC_USB") (class "Default")
      (node (ref "C141") (pin "1") (pinfunction "1_1") (pintype "passive"))
      (node (ref "C142") (pin "1") (pinfunction "1_1") (pintype "passive"))
      (node (ref "J14") (pin "1") (pinfunction "VBUS_1") (pintype "passive"))
      (node (ref "J14") (pin "10") (pinfunction "VBUS_10") (pintype "passive"))
      (node (ref "J15") (pin "1") (pinfunction "1_1") (pintype "passive"))
      (node (ref "U8") (pin "1") (pinfunction "OUT_1") (pintype "power_in"))
    )
    (net (code "44") (name "unconnected-(J13-ID-Pad4)") (class "Default")
      (node (ref "J13") (pin "4") (pinfunction "ID_4") (pintype "passive"))
    )
    (net (code "45") (name "unconnected-(J14A-StdA_SSRX+-Pad6)") (class "Default")
      (node (ref "J14") (pin "6") (pinfunction "StdA_SSRX+_6") (pintype "passive"))
    )
    (net (code "46") (name "unconnected-(J14A-StdA_SSRX--Pad5)") (class "Default")
      (node (ref "J14") (pin "5") (pinfunction "StdA_SSRX-_5") (pintype "passive"))
    )
    (net (code "47") (name "unconnected-(J14A-StdA_SSTX+-Pad9)") (class "Default")
      (node (ref "J14") (pin "9") (pinfunction "StdA_SSTX+_9") (pintype "passive"))
    )
    (net (code "48") (name "unconnected-(J14A-StdA_SSTX--Pad8)") (class "Default")
      (node (ref "J14") (pin "8") (pinfunction "StdA_SSTX-_8") (pintype "passive"))
    )
    (net (code "49") (name "unconnected-(J14B-StdA_SSRX+-Pad15)") (class "Default")
      (node (ref "J14") (pin "15") (pinfunction "StdA_SSRX+_15") (pintype "passive"))
    )
    (net (code "50") (name "unconnected-(J14B-StdA_SSRX--Pad14)") (class "Default")
      (node (ref "J14") (pin "14") (pinfunction "StdA_SSRX-_14") (pintype "passive"))
    )
    (net (code "51") (name "unconnected-(J14B-StdA_SSTX+-Pad18)") (class "Default")
      (node (ref "J14") (pin "18") (pinfunction "StdA_SSTX+_18") (pintype "passive"))
    )
    (net (code "52") (name "unconnected-(J14B-StdA_SSTX--Pad17)") (class "Default")
      (node (ref "J14") (pin "17") (pinfunction "StdA_SSTX-_17") (pintype "passive"))
    )
    (net (code "53") (name "unconnected-(J31-ID-Pad4)") (class "Default")
      (node (ref "J31") (pin "4") (pinfunction "ID_4") (pintype "passive"))
    )
    (net (code "54") (name "unconnected-(U7A-DS1_RXM-Pad7)") (class "Default")
      (node (ref "U7") (pin "7") (pinfunction "DS1_RXM_7") (pintype "passive"))
    )
    (net (code "55") (name "unconnected-(U7A-DS1_RXP-Pad6)") (class "Default")
      (node (ref "U7") (pin "6") (pinfunction "DS1_RXP_6") (pintype "passive"))
    )
    (net (code "56") (name "unconnected-(U7A-DS1_TXM-Pad4)") (class "Default")
      (node (ref "U7") (pin "4") (pinfunction "DS1_TXM_4") (pintype "passive"))
    )
    (net (code "57") (name "unconnected-(U7A-DS1_TXP-Pad3)") (class "Default")
      (node (ref "U7") (pin "3") (pinfunction "DS1_TXP_3") (pintype "passive"))
    )
    (net (code "58") (name "unconnected-(U7A-DS2_RXM-Pad16)") (class "Default")
      (node (ref "U7") (pin "16") (pinfunction "DS2_RXM_16") (pintype "passive"))
    )
    (net (code "59") (name "unconnected-(U7A-DS2_RXP-Pad15)") (class "Default")
      (node (ref "U7") (pin "15") (pinfunction "DS2_RXP_15") (pintype "passive"))
    )
    (net (code "60") (name "unconnected-(U7A-DS2_TXM-Pad13)") (class "Default")
      (node (ref "U7") (pin "13") (pinfunction "DS2_TXM_13") (pintype "passive"))
    )
    (net (code "61") (name "unconnected-(U7A-DS2_TXP-Pad12)") (class "Default")
      (node (ref "U7") (pin "12") (pinfunction "DS2_TXP_12") (pintype "passive"))
    )
    (net (code "62") (name "unconnected-(U7A-DS3_RXM-Pad29)") (class "Default")
      (node (ref "U7") (pin "29") (pinfunction "DS3_RXM_29") (pintype "passive"))
    )
    (net (code "63") (name "unconnected-(U7A-DS3_RXP-Pad28)") (class "Default")
      (node (ref "U7") (pin "28") (pinfunction "DS3_RXP_28") (pintype "passive"))
    )
    (net (code "64") (name "unconnected-(U7A-DS3_TXM-Pad26)") (class "Default")
      (node (ref "U7") (pin "26") (pinfunction "DS3_TXM_26") (pintype "passive"))
    )
    (net (code "65") (name "unconnected-(U7A-DS3_TXP-Pad25)") (class "Default")
      (node (ref "U7") (pin "25") (pinfunction "DS3_TXP_25") (pintype "passive"))
    )
    (net (code "66") (name "unconnected-(U7A-DS4_RXM-Pad35)") (class "Default")
      (node (ref "U7") (pin "35") (pinfunction "DS4_RXM_35") (pintype "passive"))
    )
    (net (code "67") (name "unconnected-(U7A-DS4_RXP-Pad34)") (class "Default")
      (node (ref "U7") (pin "34") (pinfunction "DS4_RXP_34") (pintype "passive"))
    )
    (net (code "68") (name "unconnected-(U7A-DS4_TXM-Pad32)") (class "Default")
      (node (ref "U7") (pin "32") (pinfunction "DS4_TXM_32") (pintype "passive"))
    )
    (net (code "69") (name "unconnected-(U7A-DS4_TXP-Pad31)") (class "Default")
      (node (ref "U7") (pin "31") (pinfunction "DS4_TXP_31") (pintype "passive"))
    )
    (net (code "70") (name "unconnected-(U7A-GPIO0{slash}HID0-Pad57)") (class "Default")
      (node (ref "U7") (pin "57") (pinfunction "GPIO0/HID0_57") (pintype "passive"))
    )
    (net (code "71") (name "unconnected-(U7A-GPIO1{slash}HID1-Pad58)") (class "Default")
      (node (ref "U7") (pin "58") (pinfunction "GPIO1/HID1_58") (pintype "passive"))
    )
    (net (code "72") (name "unconnected-(U7A-GPIO2{slash}HID2-Pad59)") (class "Default")
      (node (ref "U7") (pin "59") (pinfunction "GPIO2/HID2_59") (pintype "passive"))
    )
    (net (code "73") (name "unconnected-(U7A-GPIO3{slash}HID3-Pad60)") (class "Default")
      (node (ref "U7") (pin "60") (pinfunction "GPIO3/HID3_60") (pintype "passive"))
    )
    (net (code "74") (name "unconnected-(U7A-GPIO4{slash}HID4-Pad61)") (class "Default")
      (node (ref "U7") (pin "61") (pinfunction "GPIO4/HID4_61") (pintype "passive"))
    )
    (net (code "75") (name "unconnected-(U7A-GPIO5{slash}EXPWRON-Pad63)") (class "Default")
      (node (ref "U7") (pin "63") (pinfunction "GPIO5/EXPWRON_63") (pintype "passive"))
    )
    (net (code "76") (name "unconnected-(U7A-GPIO6{slash}USBSUS-Pad64)") (class "Default")
      (node (ref "U7") (pin "64") (pinfunction "GPIO6/USBSUS_64") (pintype "passive"))
    )
    (net (code "77") (name "unconnected-(U7A-GPIO7{slash}SMDAT-Pad65)") (class "Default")
      (node (ref "U7") (pin "65") (pinfunction "GPIO7/SMDAT_65") (pintype "passive"))
    )
    (net (code "78") (name "unconnected-(U7A-GPIO8{slash}SMCLK-Pad66)") (class "Default")
      (node (ref "U7") (pin "66") (pinfunction "GPIO8/SMCLK_66") (pintype "passive"))
    )
    (net (code "79") (name "unconnected-(U7A-USBLED1{slash}SPISI-Pad69)") (class "Default")
      (node (ref "U7") (pin "69") (pinfunction "USBLED1/SPISI_69") (pintype "passive"))
    )
    (net (code "80") (name "unconnected-(U7A-USBLED2{slash}SPICLK-Pad70)") (class "Default")
      (node (ref "U7") (pin "70") (pinfunction "USBLED2/SPICLK_70") (pintype "passive"))
    )
    (net (code "81") (name "unconnected-(U7A-USBLED3{slash}SPISO-Pad71)") (class "Default")
      (node (ref "U7") (pin "71") (pinfunction "USBLED3/SPISO_71") (pintype "passive"))
    )
    (net (code "82") (name "unconnected-(U7A-USBLED4{slash}SPICS-Pad72)") (class "Default")
      (node (ref "U7") (pin "72") (pinfunction "USBLED4/SPICS_72") (pintype "passive"))
    )
    (net (code "83") (name "unconnected-(U7A-US_PE0-Pad42)") (class "Default")
      (node (ref "U7") (pin "42") (pinfunction "US_PE0_42") (pintype "passive"))
    )
    (net (code "84") (name "unconnected-(U7A-US_RXM-Pad52)") (class "Default")
      (node (ref "U7") (pin "52") (pinfunction "US_RXM_52") (pintype "passive"))
    )
    (net (code "85") (name "unconnected-(U7A-US_RXP-Pad53)") (class "Default")
      (node (ref "U7") (pin "53") (pinfunction "US_RXP_53") (pintype "passive"))
    )
    (net (code "86") (name "unconnected-(U7A-US_TXM-Pad49)") (class "Default")
      (node (ref "U7") (pin "49") (pinfunction "US_TXM_49") (pintype "passive"))
    )
    (net (code "87") (name "unconnected-(U7A-US_TXP-Pad50)") (class "Default")
      (node (ref "U7") (pin "50") (pinfunction "US_TXP_50") (pintype "passive"))
    )
  )
)
